# SkateMate_Glove_Extern.net
KiCad netlist of a schematic drawn in EAGLE
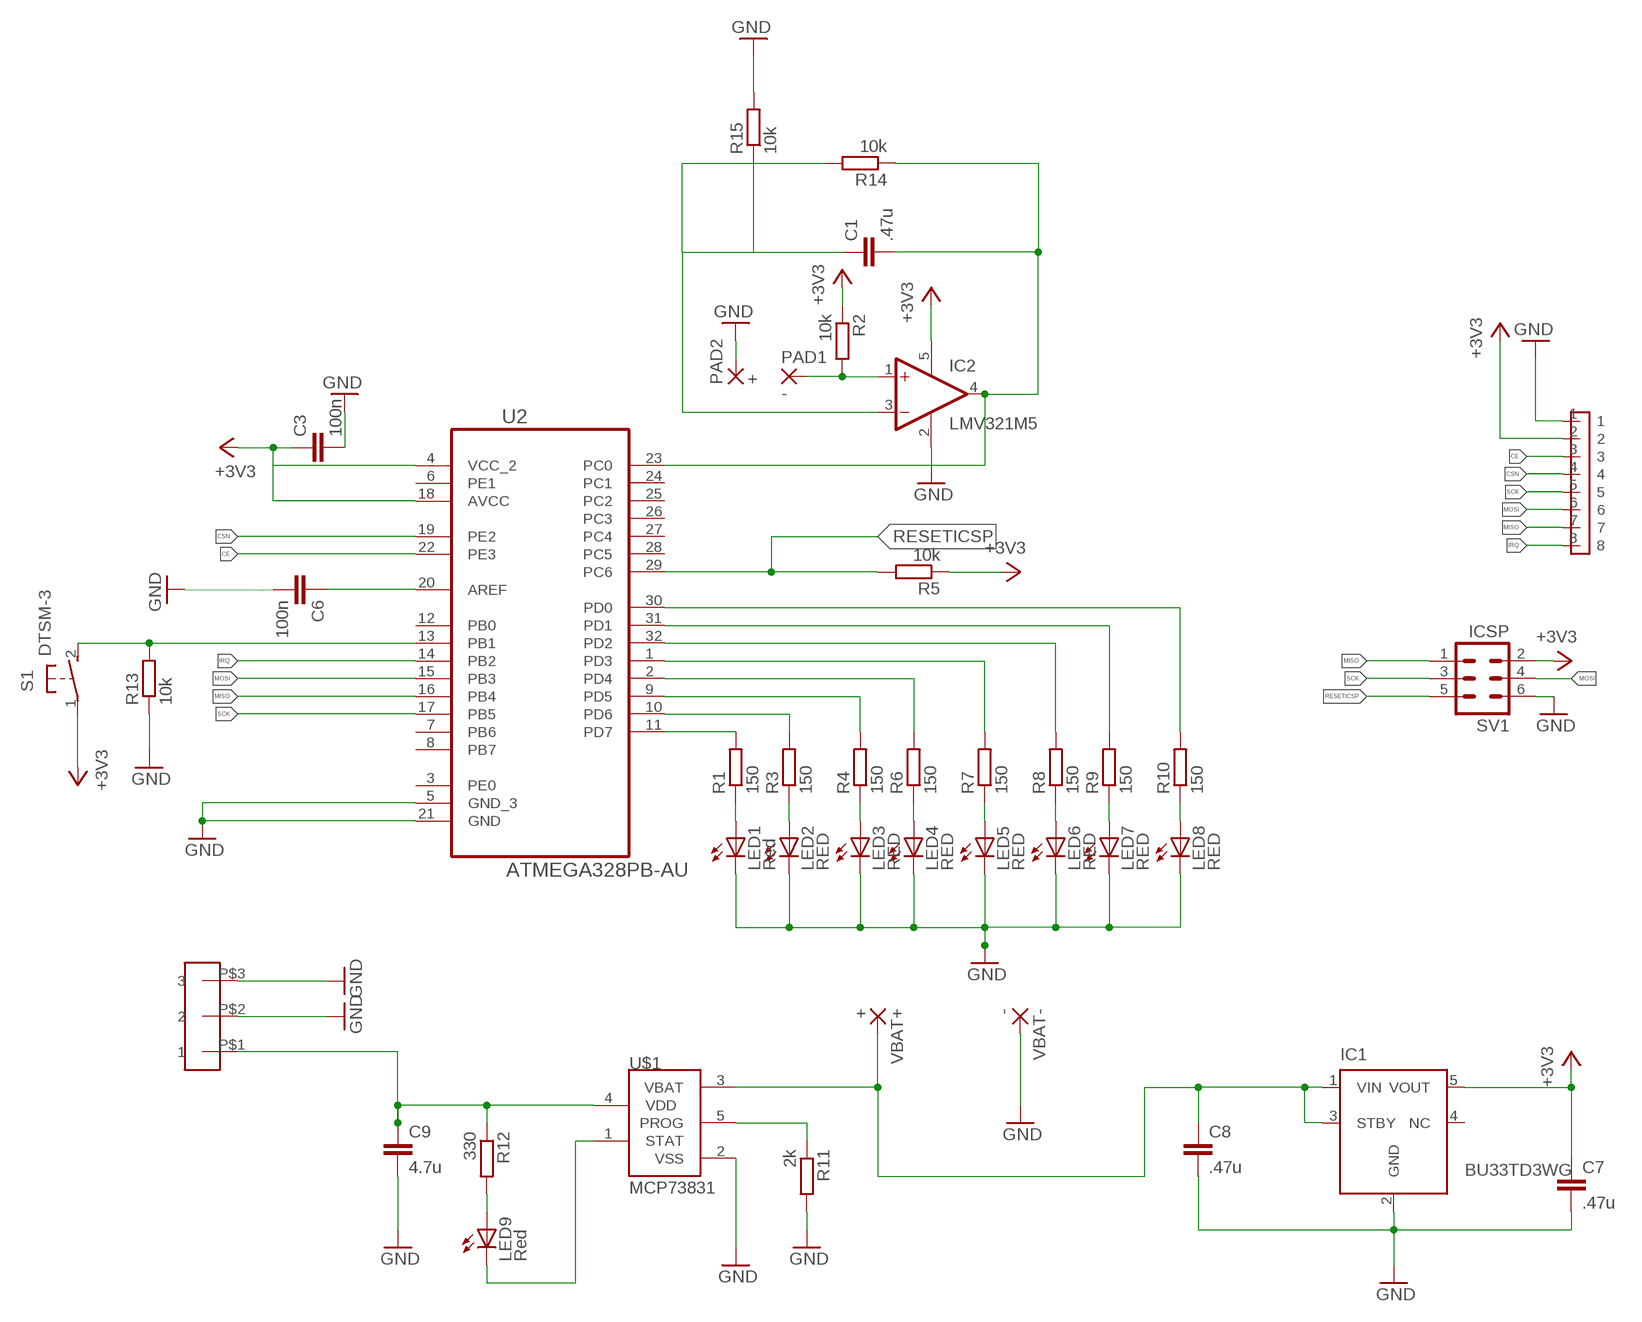
[diagram p0: schematic, sheet 1]

(export (version "E")
  (design (tool "Eeschema 10.0.6"))
  (components
    (comp (ref "C1")
      (value ".47u")
      (footprint "eagle-import:C0603")
      (libsource (lib "eagle-import") (part "CC0603"))
    )
    (comp (ref "C3")
      (value "100n")
      (footprint "eagle-import:C0603")
      (libsource (lib "eagle-import") (part "CC0603"))
    )
    (comp (ref "C6")
      (value "100n")
      (footprint "eagle-import:C0603")
      (libsource (lib "eagle-import") (part "CC0603"))
    )
    (comp (ref "C7")
      (value ".47u")
      (footprint "eagle-import:C0603")
      (libsource (lib "eagle-import") (part "CC0603"))
    )
    (comp (ref "C8")
      (value ".47u")
      (footprint "eagle-import:C0603")
      (libsource (lib "eagle-import") (part "CC0603"))
    )
    (comp (ref "C9")
      (value "4.7u")
      (footprint "eagle-import:C0603")
      (libsource (lib "eagle-import") (part "CC0603"))
    )
    (comp (ref "IC1")
      (value "BU33TD3WG")
      (footprint "eagle-import:SOT23-5")
      (libsource (lib "eagle-import") (part "BU33TD3WG-TR"))
    )
    (comp (ref "IC2")
      (value "LMV321M5")
      (footprint "eagle-import:SOT23-5")
      (libsource (lib "eagle-import") (part "LMV321?M5"))
    )
    (comp (ref "LED1")
      (value "Red")
      (footprint "eagle-import:CHIPLED_0805")
      (libsource (lib "eagle-import") (part "LEDCHIPLED_0805"))
    )
    (comp (ref "LED2")
      (value "RED")
      (footprint "eagle-import:CHIPLED_0805")
      (libsource (lib "eagle-import") (part "LEDCHIPLED_0805"))
    )
    (comp (ref "LED3")
      (value "RED")
      (footprint "eagle-import:CHIPLED_0805")
      (libsource (lib "eagle-import") (part "LEDCHIPLED_0805"))
    )
    (comp (ref "LED4")
      (value "RED")
      (footprint "eagle-import:CHIPLED_0805")
      (libsource (lib "eagle-import") (part "LEDCHIPLED_0805"))
    )
    (comp (ref "LED5")
      (value "RED")
      (footprint "eagle-import:CHIPLED_0805")
      (libsource (lib "eagle-import") (part "LEDCHIPLED_0805"))
    )
    (comp (ref "LED6")
      (value "RED")
      (footprint "eagle-import:CHIPLED_0805")
      (libsource (lib "eagle-import") (part "LEDCHIPLED_0805"))
    )
    (comp (ref "LED7")
      (value "RED")
      (footprint "eagle-import:CHIPLED_0805")
      (libsource (lib "eagle-import") (part "LEDCHIPLED_0805"))
    )
    (comp (ref "LED8")
      (value "RED")
      (footprint "eagle-import:CHIPLED_0805")
      (libsource (lib "eagle-import") (part "LEDCHIPLED_0805"))
    )
    (comp (ref "LED9")
      (value "Red")
      (footprint "eagle-import:CHIPLED_0805")
      (libsource (lib "eagle-import") (part "LEDCHIPLED_0805"))
    )
    (comp (ref "PAD1")
      (value "-")
      (footprint "eagle-import:1,6_0,8")
      (libsource (lib "eagle-import") (part "1,6/0,8"))
    )
    (comp (ref "PAD2")
      (value "+")
      (footprint "eagle-import:1,6_0,8")
      (libsource (lib "eagle-import") (part "1,6/0,8"))
    )
    (comp (ref "R1")
      (value "150")
      (footprint "eagle-import:R0603")
      (libsource (lib "eagle-import") (part "RR0603"))
    )
    (comp (ref "R2")
      (value "10k")
      (footprint "eagle-import:R0603")
      (libsource (lib "eagle-import") (part "RR0603"))
    )
    (comp (ref "R3")
      (value "150")
      (footprint "eagle-import:R0603")
      (libsource (lib "eagle-import") (part "RR0603"))
    )
    (comp (ref "R4")
      (value "150")
      (footprint "eagle-import:R0603")
      (libsource (lib "eagle-import") (part "RR0603"))
    )
    (comp (ref "R5")
      (value "10k")
      (footprint "eagle-import:R0603")
      (libsource (lib "eagle-import") (part "RR0603"))
    )
    (comp (ref "R6")
      (value "150")
      (footprint "eagle-import:R0603")
      (libsource (lib "eagle-import") (part "RR0603"))
    )
    (comp (ref "R7")
      (value "150")
      (footprint "eagle-import:R0603")
      (libsource (lib "eagle-import") (part "RR0603"))
    )
    (comp (ref "R8")
      (value "150")
      (footprint "eagle-import:R0603")
      (libsource (lib "eagle-import") (part "RR0603"))
    )
    (comp (ref "R9")
      (value "150")
      (footprint "eagle-import:R0603")
      (libsource (lib "eagle-import") (part "RR0603"))
    )
    (comp (ref "R10")
      (value "150")
      (footprint "eagle-import:R0603")
      (libsource (lib "eagle-import") (part "RR0603"))
    )
    (comp (ref "R11")
      (value "2k")
      (footprint "eagle-import:R0603")
      (libsource (lib "eagle-import") (part "RR0603"))
    )
    (comp (ref "R12")
      (value "330")
      (footprint "eagle-import:R0603")
      (libsource (lib "eagle-import") (part "RR0603"))
    )
    (comp (ref "R13")
      (value "10k")
      (footprint "eagle-import:R0603")
      (libsource (lib "eagle-import") (part "RR0603"))
    )
    (comp (ref "R14")
      (value "10k")
      (footprint "eagle-import:R0603")
      (libsource (lib "eagle-import") (part "RR0603"))
    )
    (comp (ref "R15")
      (value "10k")
      (footprint "eagle-import:R0603")
      (libsource (lib "eagle-import") (part "RR0603"))
    )
    (comp (ref "S1")
      (value "DTSM-3")
      (footprint "eagle-import:DTSM-3")
      (libsource (lib "eagle-import") (part "DTSM-3"))
    )
    (comp (ref "SV1")
      (value "ICSP")
      (footprint "eagle-import:MA03-2")
      (libsource (lib "eagle-import") (part "MA03-2"))
    )
    (comp (ref "U$1")
      (value "MCP73831")
      (footprint "eagle-import:SOT23-5L")
      (libsource (lib "eagle-import") (part "MCP73831"))
    )
    (comp (ref "U$2")
      (value "HEADER1,27")
      (footprint "eagle-import:HEADER1,27")
      (libsource (lib "eagle-import") (part "HEADER1,27"))
    )
    (comp (ref "U$3")
      (value "3PINHEADER")
      (footprint "eagle-import:3PINHEADER")
      (libsource (lib "eagle-import") (part "3PINHEADER"))
    )
    (comp (ref "U2")
      (value "ATMEGA328PB-AU")
      (footprint "eagle-import:QFP80P900X900X120-32N")
      (fields (field (name "MPN") "ATMEGA328P-AU"))
      (libsource (lib "eagle-import") (part "ATMEGA328PB-AU"))
    )
    (comp (ref "VBAT+")
      (value "+")
      (footprint "eagle-import:1,6_0,8")
      (libsource (lib "eagle-import") (part "1,6/0,8"))
    )
    (comp (ref "VBAT-")
      (value "-")
      (footprint "eagle-import:1,6_0,8")
      (libsource (lib "eagle-import") (part "1,6/0,8"))
    )
  )
  (nets
    (net (code "1") (name "+3V3") (class "Default")
      (node (ref "C3") (pin "1") (pinfunction "1_1") (pintype "passive"))
      (node (ref "C7") (pin "1") (pinfunction "1_1") (pintype "passive"))
      (node (ref "IC1") (pin "5") (pinfunction "VOUT_5") (pintype "output"))
      (node (ref "IC2") (pin "5") (pinfunction "V+_5") (pintype "power_in"))
      (node (ref "R2") (pin "1") (pinfunction "1_1") (pintype "passive"))
      (node (ref "R5") (pin "1") (pinfunction "1_1") (pintype "passive"))
      (node (ref "S1") (pin "1") (pinfunction "1_1") (pintype "passive"))
      (node (ref "SV1") (pin "2") (pinfunction "2_2") (pintype "passive"))
      (node (ref "U$2") (pin "2") (pinfunction "2_2") (pintype "bidirectional"))
      (node (ref "U2") (pin "18") (pinfunction "AVCC_18") (pintype "power_in"))
      (node (ref "U2") (pin "4") (pinfunction "VCC_2_4") (pintype "power_in"))
    )
    (net (code "2") (name "CE") (class "Default")
      (node (ref "U$2") (pin "3") (pinfunction "3_3") (pintype "bidirectional"))
      (node (ref "U2") (pin "22") (pinfunction "PE3_22") (pintype "bidirectional"))
    )
    (net (code "3") (name "CSN") (class "Default")
      (node (ref "U$2") (pin "4") (pinfunction "4_4") (pintype "bidirectional"))
      (node (ref "U2") (pin "19") (pinfunction "PE2_19") (pintype "bidirectional"))
    )
    (net (code "4") (name "GND") (class "Default")
      (node (ref "C3") (pin "2") (pinfunction "2_2") (pintype "passive"))
      (node (ref "C6") (pin "2") (pinfunction "2_2") (pintype "passive"))
      (node (ref "C7") (pin "2") (pinfunction "2_2") (pintype "passive"))
      (node (ref "C8") (pin "2") (pinfunction "2_2") (pintype "passive"))
      (node (ref "C9") (pin "2") (pinfunction "2_2") (pintype "passive"))
      (node (ref "IC1") (pin "2") (pinfunction "GND_2") (pintype "power_in"))
      (node (ref "IC2") (pin "2") (pinfunction "V-_2") (pintype "power_in"))
      (node (ref "LED1") (pin "C") (pinfunction "C_C") (pintype "passive"))
      (node (ref "LED2") (pin "C") (pinfunction "C_C") (pintype "passive"))
      (node (ref "LED3") (pin "C") (pinfunction "C_C") (pintype "passive"))
      (node (ref "LED4") (pin "C") (pinfunction "C_C") (pintype "passive"))
      (node (ref "LED5") (pin "C") (pinfunction "C_C") (pintype "passive"))
      (node (ref "LED6") (pin "C") (pinfunction "C_C") (pintype "passive"))
      (node (ref "LED7") (pin "C") (pinfunction "C_C") (pintype "passive"))
      (node (ref "LED8") (pin "C") (pinfunction "C_C") (pintype "passive"))
      (node (ref "PAD2") (pin "1") (pinfunction "P_1") (pintype "passive"))
      (node (ref "R11") (pin "2") (pinfunction "2_2") (pintype "passive"))
      (node (ref "R13") (pin "1") (pinfunction "1_1") (pintype "passive"))
      (node (ref "R15") (pin "2") (pinfunction "2_2") (pintype "passive"))
      (node (ref "SV1") (pin "6") (pinfunction "6_6") (pintype "passive"))
      (node (ref "U$1") (pin "2") (pinfunction "VSS_2") (pintype "bidirectional"))
      (node (ref "U$2") (pin "1") (pinfunction "1_1") (pintype "bidirectional"))
      (node (ref "U$3") (pin "P$2") (pinfunction "2_P$2") (pintype "bidirectional"))
      (node (ref "U$3") (pin "P$3") (pinfunction "3_P$3") (pintype "bidirectional"))
      (node (ref "U2") (pin "21") (pinfunction "GND_21") (pintype "passive"))
      (node (ref "U2") (pin "5") (pinfunction "GND_3_5") (pintype "passive"))
      (node (ref "VBAT-") (pin "1") (pinfunction "P_1") (pintype "passive"))
    )
    (net (code "5") (name "IRQ") (class "Default")
      (node (ref "U$2") (pin "8") (pinfunction "8_8") (pintype "bidirectional"))
      (node (ref "U2") (pin "14") (pinfunction "PB2_14") (pintype "bidirectional"))
    )
    (net (code "6") (name "MISO") (class "Default")
      (node (ref "SV1") (pin "1") (pinfunction "1_1") (pintype "passive"))
      (node (ref "U$2") (pin "7") (pinfunction "7_7") (pintype "bidirectional"))
      (node (ref "U2") (pin "16") (pinfunction "PB4_16") (pintype "bidirectional"))
    )
    (net (code "7") (name "MOSI") (class "Default")
      (node (ref "SV1") (pin "4") (pinfunction "4_4") (pintype "passive"))
      (node (ref "U$2") (pin "6") (pinfunction "6_6") (pintype "bidirectional"))
      (node (ref "U2") (pin "15") (pinfunction "PB3_15") (pintype "bidirectional"))
    )
    (net (code "8") (name "Net-(IC1-STBY)") (class "Default")
      (node (ref "C8") (pin "1") (pinfunction "1_1") (pintype "passive"))
      (node (ref "IC1") (pin "1") (pinfunction "VIN_1") (pintype "input"))
      (node (ref "IC1") (pin "3") (pinfunction "STBY_3") (pintype "input"))
      (node (ref "U$1") (pin "3") (pinfunction "VBAT_3") (pintype "bidirectional"))
      (node (ref "VBAT+") (pin "1") (pinfunction "P_1") (pintype "passive"))
    )
    (net (code "9") (name "Net-(IC2-+IN)") (class "Default")
      (node (ref "IC2") (pin "1") (pinfunction "+IN_1") (pintype "input"))
      (node (ref "PAD1") (pin "1") (pinfunction "P_1") (pintype "passive"))
      (node (ref "R2") (pin "2") (pinfunction "2_2") (pintype "passive"))
    )
    (net (code "10") (name "Net-(IC2--IN)") (class "Default")
      (node (ref "C1") (pin "1") (pinfunction "1_1") (pintype "passive"))
      (node (ref "IC2") (pin "3") (pinfunction "-IN_3") (pintype "input"))
      (node (ref "R14") (pin "2") (pinfunction "2_2") (pintype "passive"))
      (node (ref "R15") (pin "1") (pinfunction "1_1") (pintype "passive"))
    )
    (net (code "11") (name "Net-(IC2-OUT)") (class "Default")
      (node (ref "C1") (pin "2") (pinfunction "2_2") (pintype "passive"))
      (node (ref "IC2") (pin "4") (pinfunction "OUT_4") (pintype "output"))
      (node (ref "R14") (pin "1") (pinfunction "1_1") (pintype "passive"))
      (node (ref "U2") (pin "23") (pinfunction "PC0_23") (pintype "bidirectional"))
    )
    (net (code "12") (name "Net-(LED1-PadA)") (class "Default")
      (node (ref "LED1") (pin "A") (pinfunction "A_A") (pintype "passive"))
      (node (ref "R1") (pin "1") (pinfunction "1_1") (pintype "passive"))
    )
    (net (code "13") (name "Net-(LED2-PadA)") (class "Default")
      (node (ref "LED2") (pin "A") (pinfunction "A_A") (pintype "passive"))
      (node (ref "R3") (pin "1") (pinfunction "1_1") (pintype "passive"))
    )
    (net (code "14") (name "Net-(LED3-PadA)") (class "Default")
      (node (ref "LED3") (pin "A") (pinfunction "A_A") (pintype "passive"))
      (node (ref "R4") (pin "1") (pinfunction "1_1") (pintype "passive"))
    )
    (net (code "15") (name "Net-(LED4-PadA)") (class "Default")
      (node (ref "LED4") (pin "A") (pinfunction "A_A") (pintype "passive"))
      (node (ref "R6") (pin "1") (pinfunction "1_1") (pintype "passive"))
    )
    (net (code "16") (name "Net-(LED5-PadA)") (class "Default")
      (node (ref "LED5") (pin "A") (pinfunction "A_A") (pintype "passive"))
      (node (ref "R7") (pin "1") (pinfunction "1_1") (pintype "passive"))
    )
    (net (code "17") (name "Net-(LED6-PadA)") (class "Default")
      (node (ref "LED6") (pin "A") (pinfunction "A_A") (pintype "passive"))
      (node (ref "R8") (pin "1") (pinfunction "1_1") (pintype "passive"))
    )
    (net (code "18") (name "Net-(LED7-PadA)") (class "Default")
      (node (ref "LED7") (pin "A") (pinfunction "A_A") (pintype "passive"))
      (node (ref "R9") (pin "1") (pinfunction "1_1") (pintype "passive"))
    )
    (net (code "19") (name "Net-(LED8-PadA)") (class "Default")
      (node (ref "LED8") (pin "A") (pinfunction "A_A") (pintype "passive"))
      (node (ref "R10") (pin "1") (pinfunction "1_1") (pintype "passive"))
    )
    (net (code "20") (name "Net-(LED9-PadA)") (class "Default")
      (node (ref "LED9") (pin "A") (pinfunction "A_A") (pintype "passive"))
      (node (ref "R12") (pin "2") (pinfunction "2_2") (pintype "passive"))
    )
    (net (code "21") (name "Net-(U$1-PROG)") (class "Default")
      (node (ref "R11") (pin "1") (pinfunction "1_1") (pintype "passive"))
      (node (ref "U$1") (pin "5") (pinfunction "PROG_5") (pintype "bidirectional"))
    )
    (net (code "22") (name "Net-(U$1-STAT)") (class "Default")
      (node (ref "LED9") (pin "C") (pinfunction "C_C") (pintype "passive"))
      (node (ref "U$1") (pin "1") (pinfunction "STAT_1") (pintype "bidirectional"))
    )
    (net (code "23") (name "Net-(U$1-VDD)") (class "Default")
      (node (ref "C9") (pin "1") (pinfunction "1_1") (pintype "passive"))
      (node (ref "R12") (pin "1") (pinfunction "1_1") (pintype "passive"))
      (node (ref "U$1") (pin "4") (pinfunction "VDD_4") (pintype "bidirectional"))
      (node (ref "U$3") (pin "P$1") (pinfunction "1_P$1") (pintype "bidirectional"))
    )
    (net (code "24") (name "Net-(U2-AREF)") (class "Default")
      (node (ref "C6") (pin "1") (pinfunction "1_1") (pintype "passive"))
      (node (ref "U2") (pin "20") (pinfunction "AREF_20") (pintype "input"))
    )
    (net (code "25") (name "Net-(U2-PB1)") (class "Default")
      (node (ref "R13") (pin "2") (pinfunction "2_2") (pintype "passive"))
      (node (ref "S1") (pin "2") (pinfunction "2_2") (pintype "passive"))
      (node (ref "U2") (pin "13") (pinfunction "PB1_13") (pintype "bidirectional"))
    )
    (net (code "26") (name "Net-(U2-PD0)") (class "Default")
      (node (ref "R10") (pin "2") (pinfunction "2_2") (pintype "passive"))
      (node (ref "U2") (pin "30") (pinfunction "PD0_30") (pintype "bidirectional"))
    )
    (net (code "27") (name "Net-(U2-PD1)") (class "Default")
      (node (ref "R9") (pin "2") (pinfunction "2_2") (pintype "passive"))
      (node (ref "U2") (pin "31") (pinfunction "PD1_31") (pintype "bidirectional"))
    )
    (net (code "28") (name "Net-(U2-PD2)") (class "Default")
      (node (ref "R8") (pin "2") (pinfunction "2_2") (pintype "passive"))
      (node (ref "U2") (pin "32") (pinfunction "PD2_32") (pintype "bidirectional"))
    )
    (net (code "29") (name "Net-(U2-PD3)") (class "Default")
      (node (ref "R7") (pin "2") (pinfunction "2_2") (pintype "passive"))
      (node (ref "U2") (pin "1") (pinfunction "PD3_1") (pintype "bidirectional"))
    )
    (net (code "30") (name "Net-(U2-PD4)") (class "Default")
      (node (ref "R6") (pin "2") (pinfunction "2_2") (pintype "passive"))
      (node (ref "U2") (pin "2") (pinfunction "PD4_2") (pintype "bidirectional"))
    )
    (net (code "31") (name "Net-(U2-PD5)") (class "Default")
      (node (ref "R4") (pin "2") (pinfunction "2_2") (pintype "passive"))
      (node (ref "U2") (pin "9") (pinfunction "PD5_9") (pintype "bidirectional"))
    )
    (net (code "32") (name "Net-(U2-PD6)") (class "Default")
      (node (ref "R3") (pin "2") (pinfunction "2_2") (pintype "passive"))
      (node (ref "U2") (pin "10") (pinfunction "PD6_10") (pintype "bidirectional"))
    )
    (net (code "33") (name "Net-(U2-PD7)") (class "Default")
      (node (ref "R1") (pin "2") (pinfunction "2_2") (pintype "passive"))
      (node (ref "U2") (pin "11") (pinfunction "PD7_11") (pintype "bidirectional"))
    )
    (net (code "34") (name "RESETICSP") (class "Default")
      (node (ref "R5") (pin "2") (pinfunction "2_2") (pintype "passive"))
      (node (ref "SV1") (pin "5") (pinfunction "5_5") (pintype "passive"))
      (node (ref "U2") (pin "29") (pinfunction "PC6_29") (pintype "bidirectional"))
    )
    (net (code "35") (name "SCK") (class "Default")
      (node (ref "SV1") (pin "3") (pinfunction "3_3") (pintype "passive"))
      (node (ref "U$2") (pin "5") (pinfunction "5_5") (pintype "bidirectional"))
      (node (ref "U2") (pin "17") (pinfunction "PB5_17") (pintype "bidirectional"))
    )
    (net (code "36") (name "unconnected-(IC1-NC-Pad4)") (class "Default")
      (node (ref "IC1") (pin "4") (pinfunction "NC_4") (pintype "passive"))
    )
    (net (code "37") (name "unconnected-(U2-PB0-Pad12)") (class "Default")
      (node (ref "U2") (pin "12") (pinfunction "PB0_12") (pintype "bidirectional"))
    )
    (net (code "38") (name "unconnected-(U2-PB6-Pad7)") (class "Default")
      (node (ref "U2") (pin "7") (pinfunction "PB6_7") (pintype "bidirectional"))
    )
    (net (code "39") (name "unconnected-(U2-PB7-Pad8)") (class "Default")
      (node (ref "U2") (pin "8") (pinfunction "PB7_8") (pintype "bidirectional"))
    )
    (net (code "40") (name "unconnected-(U2-PC1-Pad24)") (class "Default")
      (node (ref "U2") (pin "24") (pinfunction "PC1_24") (pintype "bidirectional"))
    )
    (net (code "41") (name "unconnected-(U2-PC2-Pad25)") (class "Default")
      (node (ref "U2") (pin "25") (pinfunction "PC2_25") (pintype "bidirectional"))
    )
    (net (code "42") (name "unconnected-(U2-PC3-Pad26)") (class "Default")
      (node (ref "U2") (pin "26") (pinfunction "PC3_26") (pintype "bidirectional"))
    )
    (net (code "43") (name "unconnected-(U2-PC4-Pad27)") (class "Default")
      (node (ref "U2") (pin "27") (pinfunction "PC4_27") (pintype "bidirectional"))
    )
    (net (code "44") (name "unconnected-(U2-PC5-Pad28)") (class "Default")
      (node (ref "U2") (pin "28") (pinfunction "PC5_28") (pintype "bidirectional"))
    )
    (net (code "45") (name "unconnected-(U2-PE0-Pad3)") (class "Default")
      (node (ref "U2") (pin "3") (pinfunction "PE0_3") (pintype "bidirectional"))
    )
    (net (code "46") (name "unconnected-(U2-PE1-Pad6)") (class "Default")
      (node (ref "U2") (pin "6") (pinfunction "PE1_6") (pintype "bidirectional"))
    )
  )
)
